# timer.net
KiCad netlist of a schematic drawn in EasyEDA Pro
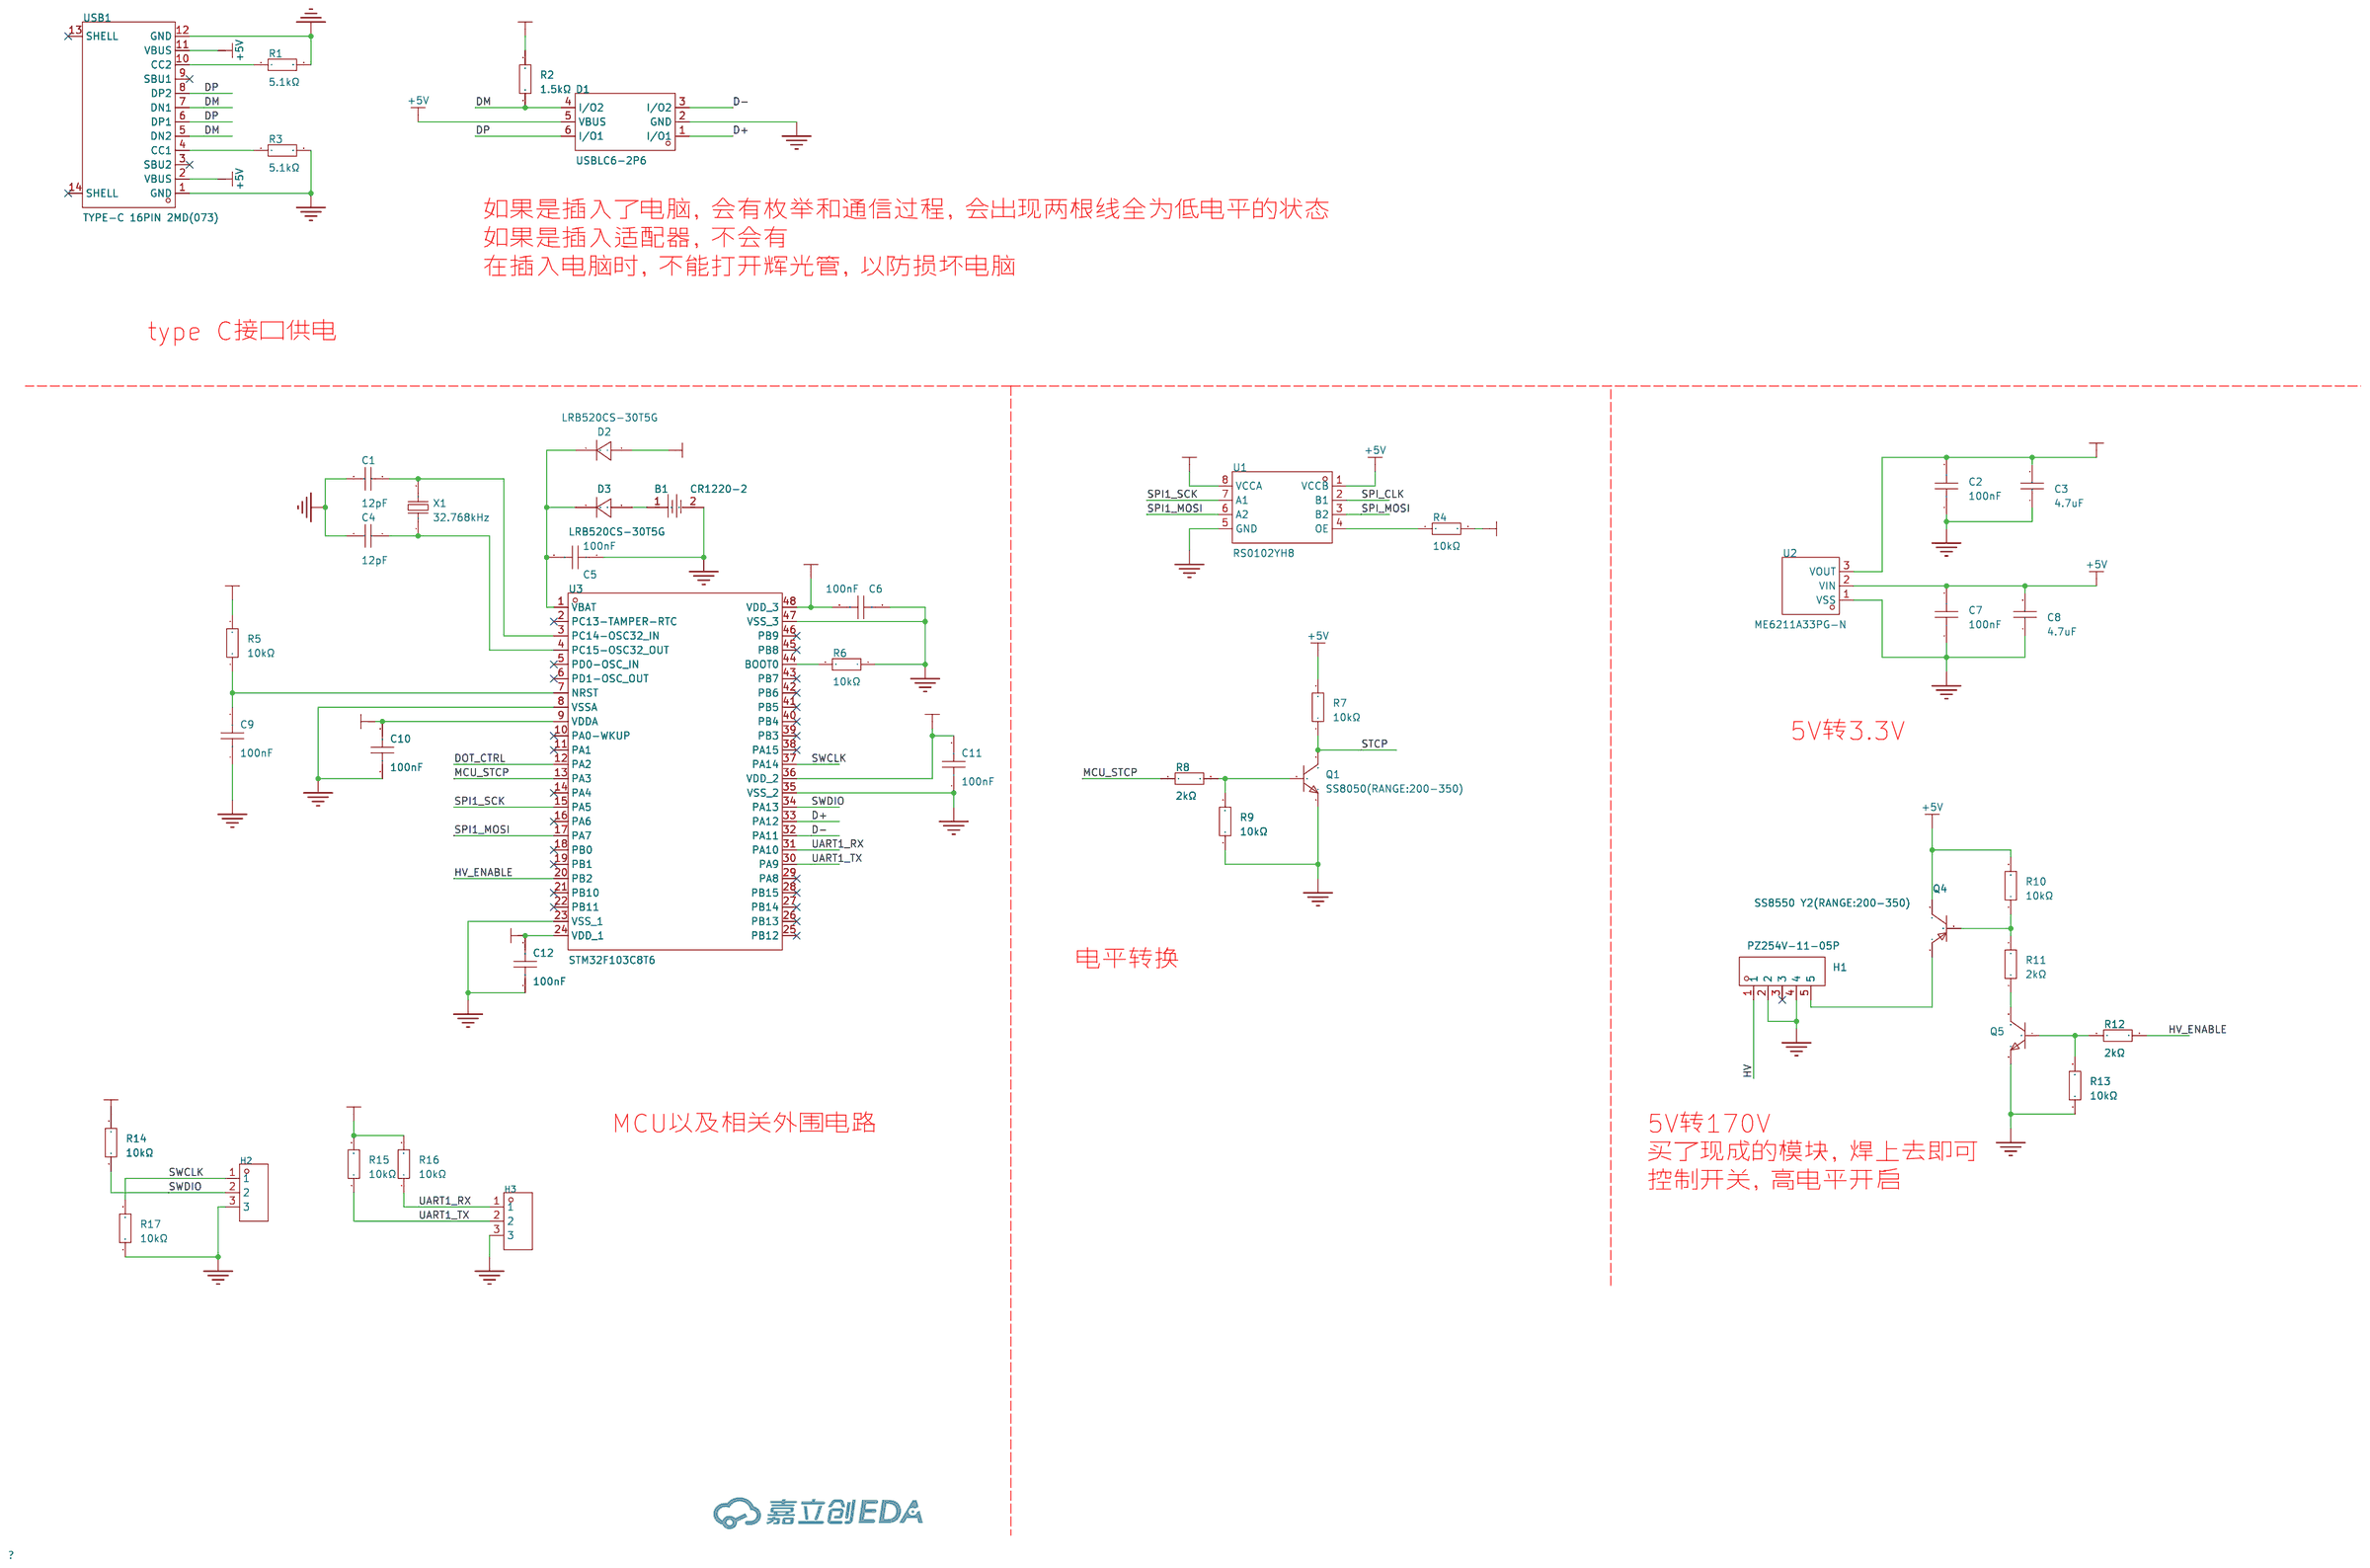
[diagram p0: 控制部分]
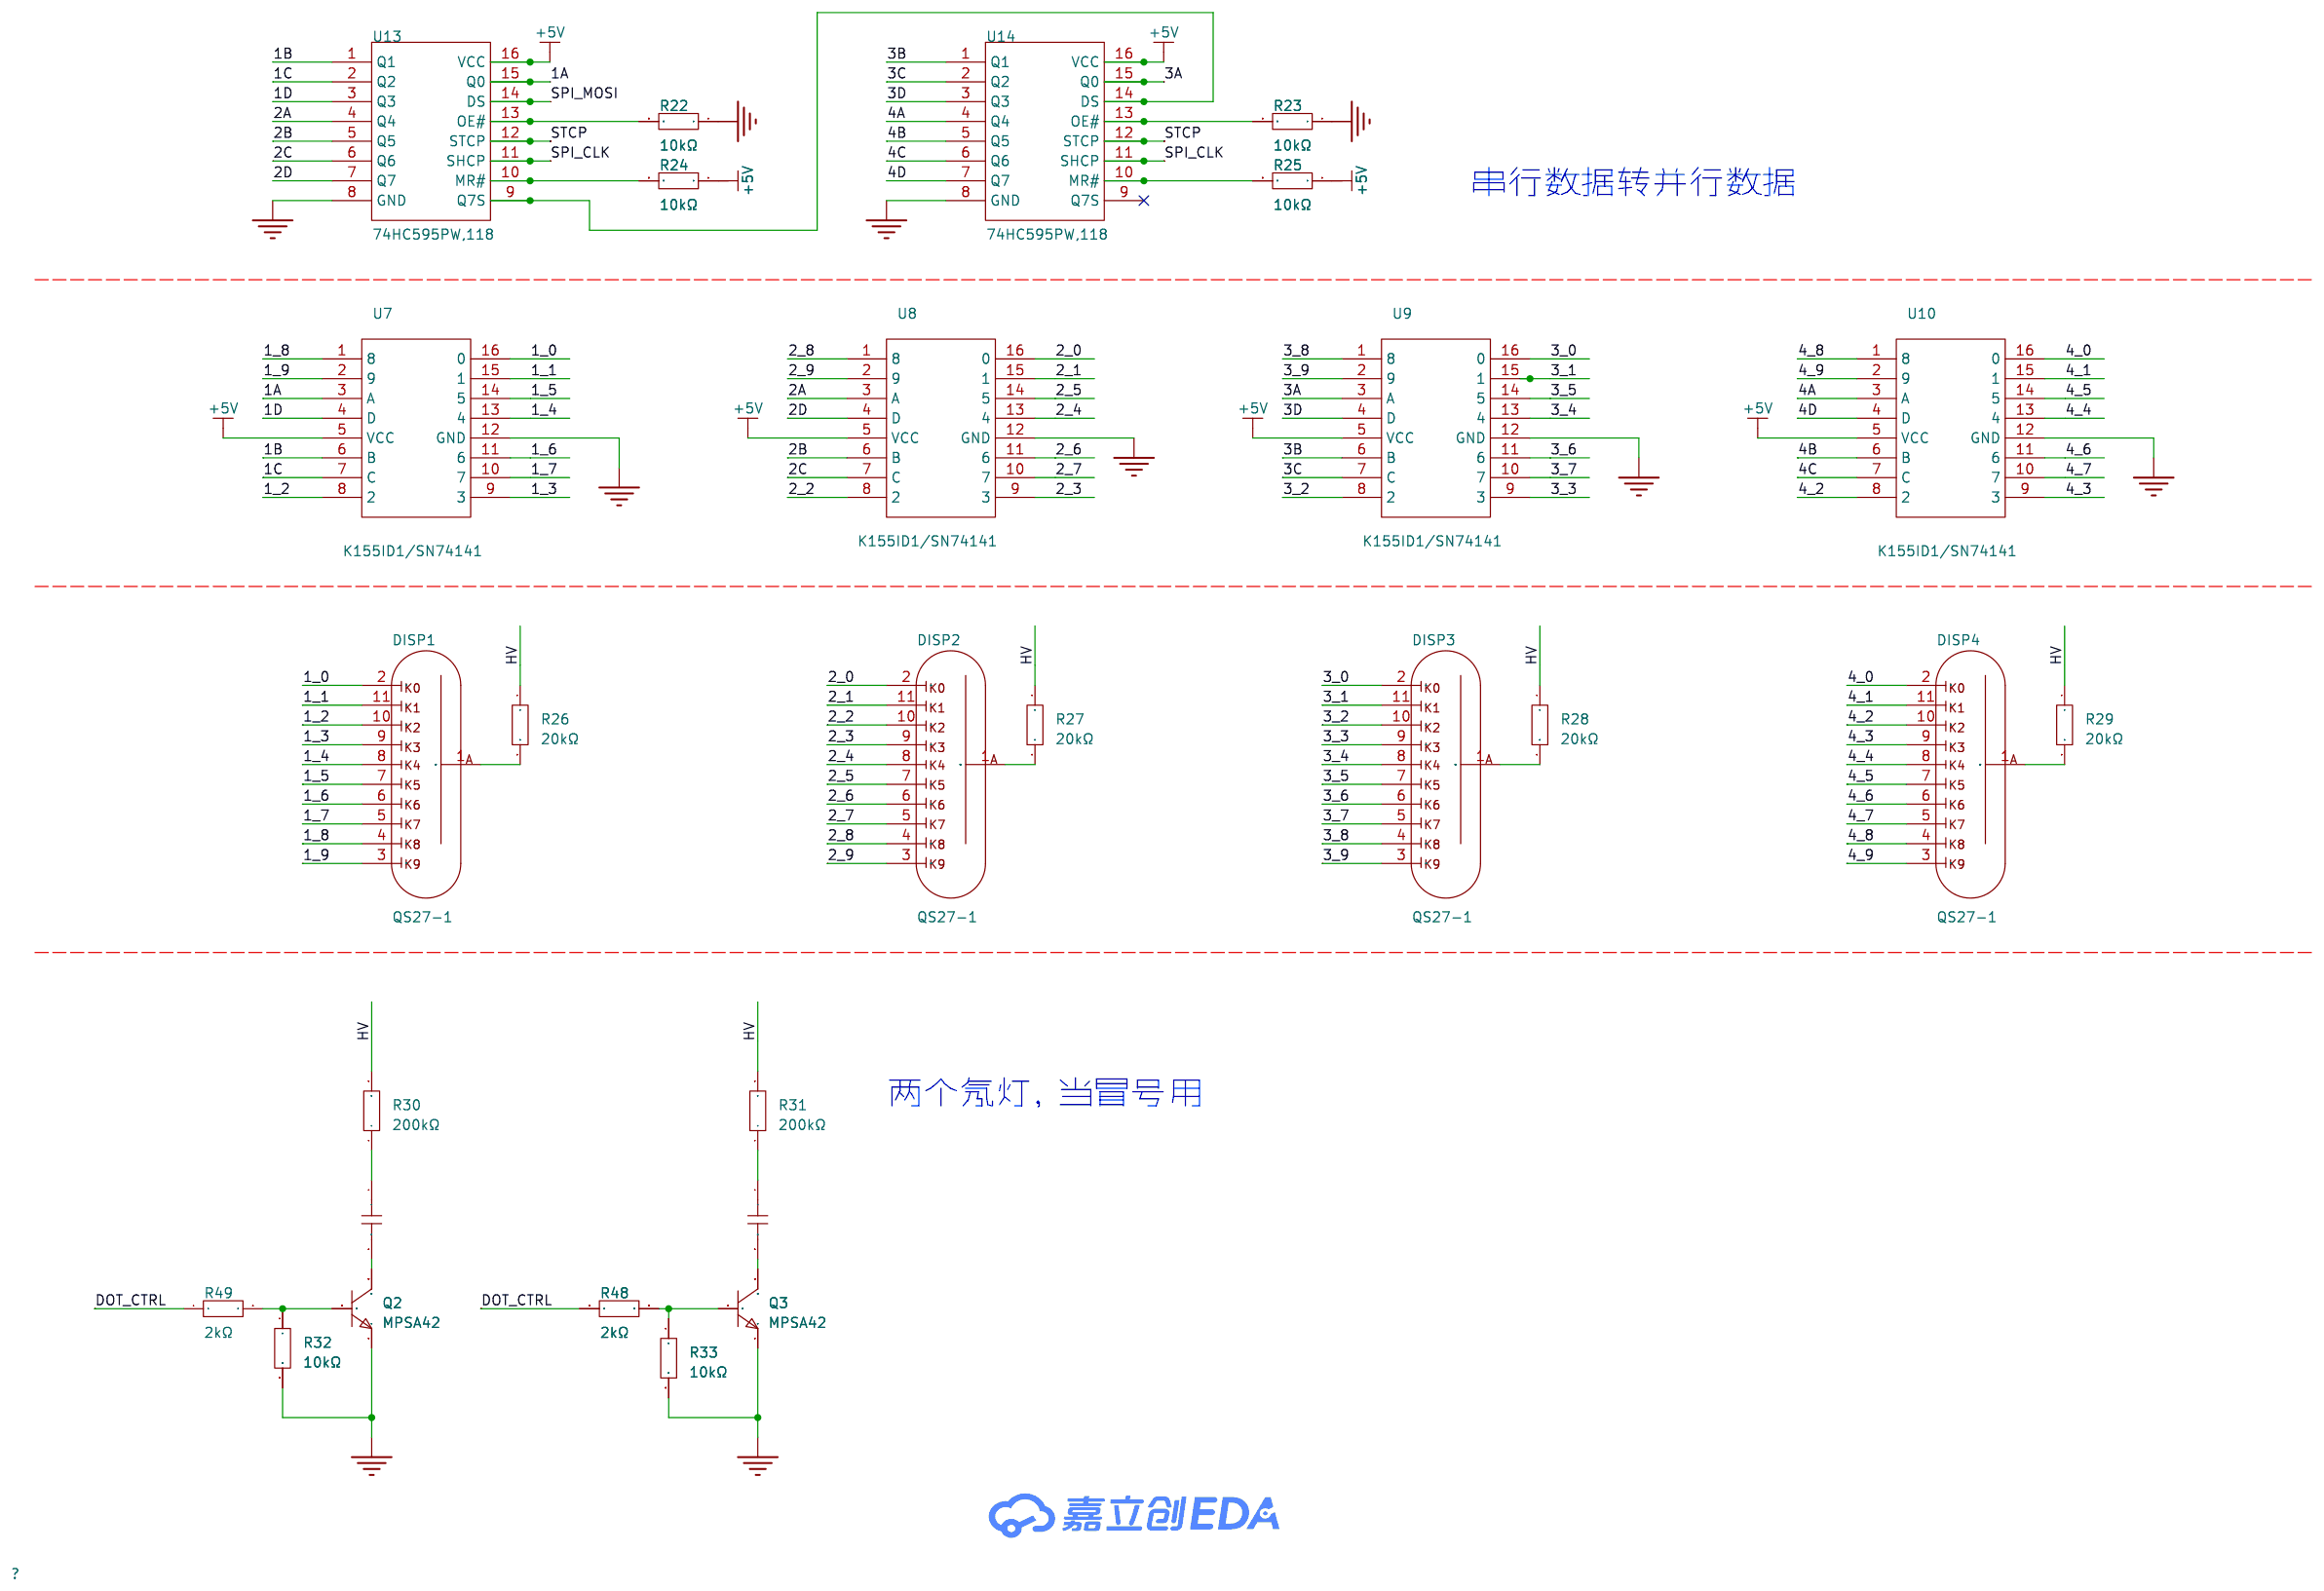
[diagram p1: 显示部分]

(export (version "E")
  (design (tool "Eeschema 10.0.6"))
  (components
    (comp (ref "B1")
      (value "CR1220-2")
      (footprint "easyedapro:BAT-SMD_CR1220-2")
      (description "连接器类型:电池底座;适用电池规格:CR1220;工作温度范围:-;")
      (fields (field (name "Manufacturer") "Q&J"))
      (libsource (lib "easyedapro") (part "CR1220-2"))
    )
    (comp (ref "C1")
      (value "12pF")
      (footprint "easyedapro:C0603")
      (description "容值:12pF;精度:±5%;额定电压:50V;材质(温度系数):NP0;")
      (fields
        (field (name "Manufacturer Part") "CC0603JRNPO9BN120")
        (field (name "Manufacturer") "YAGEO(国巨)")
      )
      (libsource (lib "easyedapro") (part "CC0603JRNPO9BN120"))
    )
    (comp (ref "C2")
      (value "100nF")
      (footprint "easyedapro:C0603")
      (description "容值:100nF;精度:±10%;额定电压:50V;材质(温度系数):X7R;")
      (fields
        (field (name "Manufacturer Part") "CC0603KRX7R9BB104")
        (field (name "Manufacturer") "YAGEO(国巨)")
      )
      (libsource (lib "easyedapro") (part "CC0603KRX7R9BB104"))
    )
    (comp (ref "C3")
      (value "4.7uF")
      (footprint "easyedapro:C0603")
      (description "容值:4.7uF;精度:±10%;额定电压:16V;材质(温度系数):X5R;")
      (fields
        (field (name "Manufacturer Part") "CL10A475KO8NNNC")
        (field (name "Manufacturer") "SAMSUNG(三星)")
      )
      (libsource (lib "easyedapro") (part "CL10A475KO8NNNC"))
    )
    (comp (ref "C4")
      (value "12pF")
      (footprint "easyedapro:C0603")
      (description "容值:12pF;精度:±5%;额定电压:50V;材质(温度系数):NP0;")
      (fields
        (field (name "Manufacturer Part") "CC0603JRNPO9BN120")
        (field (name "Manufacturer") "YAGEO(国巨)")
      )
      (libsource (lib "easyedapro") (part "CC0603JRNPO9BN120"))
    )
    (comp (ref "C5")
      (value "100nF")
      (footprint "easyedapro:C0603")
      (description "容值:100nF;精度:±10%;额定电压:50V;材质(温度系数):X7R;")
      (fields
        (field (name "Manufacturer Part") "CC0603KRX7R9BB104")
        (field (name "Manufacturer") "YAGEO(国巨)")
      )
      (libsource (lib "easyedapro") (part "CC0603KRX7R9BB104"))
    )
    (comp (ref "C6")
      (value "100nF")
      (footprint "easyedapro:C0603")
      (description "容值:100nF;精度:±10%;额定电压:50V;材质(温度系数):X7R;")
      (fields
        (field (name "Manufacturer Part") "CC0603KRX7R9BB104")
        (field (name "Manufacturer") "YAGEO(国巨)")
      )
      (libsource (lib "easyedapro") (part "CC0603KRX7R9BB104"))
    )
    (comp (ref "C7")
      (value "100nF")
      (footprint "easyedapro:C0603")
      (description "容值:100nF;精度:±10%;额定电压:50V;材质(温度系数):X7R;")
      (fields
        (field (name "Manufacturer Part") "CC0603KRX7R9BB104")
        (field (name "Manufacturer") "YAGEO(国巨)")
      )
      (libsource (lib "easyedapro") (part "CC0603KRX7R9BB104"))
    )
    (comp (ref "C8")
      (value "4.7uF")
      (footprint "easyedapro:C0603")
      (description "容值:4.7uF;精度:±10%;额定电压:16V;材质(温度系数):X5R;")
      (fields
        (field (name "Manufacturer Part") "CL10A475KO8NNNC")
        (field (name "Manufacturer") "SAMSUNG(三星)")
      )
      (libsource (lib "easyedapro") (part "CL10A475KO8NNNC"))
    )
    (comp (ref "C9")
      (value "100nF")
      (footprint "easyedapro:C0603")
      (description "容值:100nF;精度:±10%;额定电压:50V;材质(温度系数):X7R;")
      (fields
        (field (name "Manufacturer Part") "CC0603KRX7R9BB104")
        (field (name "Manufacturer") "YAGEO(国巨)")
      )
      (libsource (lib "easyedapro") (part "CC0603KRX7R9BB104"))
    )
    (comp (ref "C10")
      (value "100nF")
      (footprint "easyedapro:C0603")
      (description "容值:100nF;精度:±10%;额定电压:50V;材质(温度系数):X7R;")
      (fields
        (field (name "Manufacturer Part") "CC0603KRX7R9BB104")
        (field (name "Manufacturer") "YAGEO(国巨)")
      )
      (libsource (lib "easyedapro") (part "CC0603KRX7R9BB104"))
    )
    (comp (ref "C11")
      (value "100nF")
      (footprint "easyedapro:C0603")
      (description "容值:100nF;精度:±10%;额定电压:50V;材质(温度系数):X7R;")
      (fields
        (field (name "Manufacturer Part") "CC0603KRX7R9BB104")
        (field (name "Manufacturer") "YAGEO(国巨)")
      )
      (libsource (lib "easyedapro") (part "CC0603KRX7R9BB104"))
    )
    (comp (ref "C12")
      (value "100nF")
      (footprint "easyedapro:C0603")
      (description "容值:100nF;精度:±10%;额定电压:50V;材质(温度系数):X7R;")
      (fields
        (field (name "Manufacturer Part") "CC0603KRX7R9BB104")
        (field (name "Manufacturer") "YAGEO(国巨)")
      )
      (libsource (lib "easyedapro") (part "CC0603KRX7R9BB104"))
    )
    (comp (ref "D1")
      (value "USBLC6-2P6")
      (footprint "easyedapro:SOT-666-6_L1.6-W1.2-P0.50-LS1.6-BL")
      (description "极性:单向;反向截止电压(Vrwm):5V;最大钳位电压:14V;峰值脉冲电流(Ipp):5.5A;峰值脉冲功率(Ppp):80W;击穿电压:6V;")
      (fields (field (name "Manufacturer") "TECH PUBLIC(台舟)"))
      (libsource (lib "easyedapro") (part "USBLC6-2P6_C2827693"))
    )
    (comp (ref "D2")
      (value "LRB520CS-30T5G")
      (footprint "easyedapro:SOD-923_L0.8-W0.6-LS1.0-RD")
      (description "正向压降(Vf):450mV;直流反向耐压(Vr):30V;整流电流:100mA;")
      (fields (field (name "Manufacturer") "LRC(乐山无线电)"))
      (libsource (lib "easyedapro") (part "LRB520CS-30T5G"))
    )
    (comp (ref "D3")
      (value "LRB520CS-30T5G")
      (footprint "easyedapro:SOD-923_L0.8-W0.6-LS1.0-RD")
      (description "正向压降(Vf):450mV;直流反向耐压(Vr):30V;整流电流:100mA;")
      (fields (field (name "Manufacturer") "LRC(乐山无线电)"))
      (libsource (lib "easyedapro") (part "LRB520CS-30T5G"))
    )
    (comp (ref "H1")
      (value "PZ254V-11-05P")
      (footprint "easyedapro:HDR-TH_5P-P2.54-V-M")
      (fields (field (name "Manufacturer") "XFCN(兴飞)"))
      (libsource (lib "easyedapro") (part "PZ254V-11-05P"))
    )
    (comp (ref "H2")
      (value "PZ254V-11-03P")
      (footprint "easyedapro:HDR-TH_3P-P2.54-V-M")
      (fields (field (name "Manufacturer") "XFCN(兴飞)"))
      (libsource (lib "easyedapro") (part "PZ254V-11-03P_C2937625"))
    )
    (comp (ref "H3")
      (value "PZ254V-11-03P")
      (footprint "easyedapro:HDR-TH_3P-P2.54-V-M")
      (fields (field (name "Manufacturer") "XFCN(兴飞)"))
      (libsource (lib "easyedapro") (part "PZ254V-11-03P_C2937625"))
    )
    (comp (ref "Q1")
      (value "SS8050(RANGE:200-350)")
      (footprint "easyedapro:SOT-23-3_L2.9-W1.3-P1.90-LS2.4-BR")
      (description "晶体管类型:NPN;集电极电流(Ic):1.5A;集射极击穿电压(Vceo):25V;功率(Pd):300mW;直流电流增益(hFE@Ic,Vce):200@800mA,1V;")
      (fields (field (name "Manufacturer") "CJ(江苏长电/长晶)"))
      (libsource (lib "easyedapro") (part "SS8050_C2150"))
    )
    (comp (ref "Q4")
      (value "SS8550 Y2(RANGE:200-350)")
      (footprint "easyedapro:SOT-23-3_L2.9-W1.3-P1.90-LS2.4-BR")
      (description "晶体管类型:PNP;集电极电流(Ic):1.5A;集射极击穿电压(Vceo):25V;功率(Pd):300mW;直流电流增益(hFE@Ic,Vce):200@100mA,1V;")
      (fields (field (name "Manufacturer") "CJ(江苏长电/长晶)"))
      (libsource (lib "easyedapro") (part "SS8550_C8542"))
    )
    (comp (ref "Q5")
      (value "SS8050(RANGE:200-350)")
      (footprint "easyedapro:SOT-23-3_L2.9-W1.3-P1.90-LS2.4-BR")
      (description "晶体管类型:NPN;集电极电流(Ic):1.5A;集射极击穿电压(Vceo):25V;功率(Pd):300mW;直流电流增益(hFE@Ic,Vce):200@800mA,1V;")
      (fields (field (name "Manufacturer") "CJ(江苏长电/长晶)"))
      (libsource (lib "easyedapro") (part "SS8050_C2150"))
    )
    (comp (ref "R1")
      (value "5.1kΩ")
      (footprint "easyedapro:R0603")
      (description "电阻类型:厚膜电阻;阻值:5.1kΩ;精度:±1%;功率:100mW;最大工作电压:75V;温度系数:±100ppm/°C;")
      (fields
        (field (name "Manufacturer Part") "0603WAF5101T5E")
        (field (name "Manufacturer") "UNI-ROYAL(厚声)")
      )
      (libsource (lib "easyedapro") (part "0603WAF5101T5E"))
    )
    (comp (ref "R2")
      (value "1.5kΩ")
      (footprint "easyedapro:R0603")
      (description "电阻类型:厚膜电阻;阻值:1.5kΩ;精度:±1%;功率:100mW;最大工作电压:75V;温度系数:±100ppm/°C;")
      (fields
        (field (name "Manufacturer Part") "0603WAF1501T5E")
        (field (name "Manufacturer") "UNI-ROYAL(厚声)")
      )
      (libsource (lib "easyedapro") (part "0603WAF1501T5E"))
    )
    (comp (ref "R3")
      (value "5.1kΩ")
      (footprint "easyedapro:R0603")
      (description "电阻类型:厚膜电阻;阻值:5.1kΩ;精度:±1%;功率:100mW;最大工作电压:75V;温度系数:±100ppm/°C;")
      (fields
        (field (name "Manufacturer Part") "0603WAF5101T5E")
        (field (name "Manufacturer") "UNI-ROYAL(厚声)")
      )
      (libsource (lib "easyedapro") (part "0603WAF5101T5E"))
    )
    (comp (ref "R4")
      (value "10kΩ")
      (footprint "easyedapro:R0603")
      (description "电阻类型:厚膜电阻;阻值:10kΩ;精度:±1%;功率:100mW;最大工作电压:75V;温度系数:±100ppm/°C;")
      (fields
        (field (name "Manufacturer Part") "0603WAF1002T5E")
        (field (name "Manufacturer") "UNI-ROYAL(厚声)")
      )
      (libsource (lib "easyedapro") (part "0603WAF1002T5E"))
    )
    (comp (ref "R5")
      (value "10kΩ")
      (footprint "easyedapro:R0603")
      (description "电阻类型:厚膜电阻;阻值:10kΩ;精度:±1%;功率:100mW;最大工作电压:75V;温度系数:±100ppm/°C;")
      (fields
        (field (name "Manufacturer Part") "0603WAF1002T5E")
        (field (name "Manufacturer") "UNI-ROYAL(厚声)")
      )
      (libsource (lib "easyedapro") (part "0603WAF1002T5E"))
    )
    (comp (ref "R6")
      (value "10kΩ")
      (footprint "easyedapro:R0603")
      (description "电阻类型:厚膜电阻;阻值:10kΩ;精度:±1%;功率:100mW;最大工作电压:75V;温度系数:±100ppm/°C;")
      (fields
        (field (name "Manufacturer Part") "0603WAF1002T5E")
        (field (name "Manufacturer") "UNI-ROYAL(厚声)")
      )
      (libsource (lib "easyedapro") (part "0603WAF1002T5E"))
    )
    (comp (ref "R7")
      (value "10kΩ")
      (footprint "easyedapro:R0603")
      (description "电阻类型:厚膜电阻;阻值:10kΩ;精度:±1%;功率:100mW;最大工作电压:75V;温度系数:±100ppm/°C;")
      (fields
        (field (name "Manufacturer Part") "0603WAF1002T5E")
        (field (name "Manufacturer") "UNI-ROYAL(厚声)")
      )
      (libsource (lib "easyedapro") (part "0603WAF1002T5E"))
    )
    (comp (ref "R8")
      (value "2kΩ")
      (footprint "easyedapro:R0603")
      (description "电阻类型:厚膜电阻;阻值:2kΩ;精度:±1%;功率:100mW;最大工作电压:75V;温度系数:±100ppm/°C;")
      (fields
        (field (name "Manufacturer Part") "0603WAF2001T5E")
        (field (name "Manufacturer") "UNI-ROYAL(厚声)")
      )
      (libsource (lib "easyedapro") (part "0603WAF2001T5E"))
    )
    (comp (ref "R9")
      (value "10kΩ")
      (footprint "easyedapro:R0603")
      (description "电阻类型:厚膜电阻;阻值:10kΩ;精度:±1%;功率:100mW;最大工作电压:75V;温度系数:±100ppm/°C;")
      (fields
        (field (name "Manufacturer Part") "0603WAF1002T5E")
        (field (name "Manufacturer") "UNI-ROYAL(厚声)")
      )
      (libsource (lib "easyedapro") (part "0603WAF1002T5E"))
    )
    (comp (ref "R10")
      (value "10kΩ")
      (footprint "easyedapro:R0603")
      (description "电阻类型:厚膜电阻;阻值:10kΩ;精度:±1%;功率:100mW;最大工作电压:75V;温度系数:±100ppm/°C;")
      (fields
        (field (name "Manufacturer Part") "0603WAF1002T5E")
        (field (name "Manufacturer") "UNI-ROYAL(厚声)")
      )
      (libsource (lib "easyedapro") (part "0603WAF1002T5E"))
    )
    (comp (ref "R11")
      (value "2kΩ")
      (footprint "easyedapro:R0603")
      (description "电阻类型:厚膜电阻;阻值:2kΩ;精度:±1%;功率:100mW;最大工作电压:75V;温度系数:±100ppm/°C;")
      (fields
        (field (name "Manufacturer Part") "0603WAF2001T5E")
        (field (name "Manufacturer") "UNI-ROYAL(厚声)")
      )
      (libsource (lib "easyedapro") (part "0603WAF2001T5E"))
    )
    (comp (ref "R12")
      (value "2kΩ")
      (footprint "easyedapro:R0603")
      (description "电阻类型:厚膜电阻;阻值:2kΩ;精度:±1%;功率:100mW;最大工作电压:75V;温度系数:±100ppm/°C;")
      (fields
        (field (name "Manufacturer Part") "0603WAF2001T5E")
        (field (name "Manufacturer") "UNI-ROYAL(厚声)")
      )
      (libsource (lib "easyedapro") (part "0603WAF2001T5E"))
    )
    (comp (ref "R13")
      (value "10kΩ")
      (footprint "easyedapro:R0603")
      (description "电阻类型:厚膜电阻;阻值:10kΩ;精度:±1%;功率:100mW;最大工作电压:75V;温度系数:±100ppm/°C;")
      (fields
        (field (name "Manufacturer Part") "0603WAF1002T5E")
        (field (name "Manufacturer") "UNI-ROYAL(厚声)")
      )
      (libsource (lib "easyedapro") (part "0603WAF1002T5E"))
    )
    (comp (ref "R14")
      (value "10kΩ")
      (footprint "easyedapro:R0603")
      (description "电阻类型:厚膜电阻;阻值:10kΩ;精度:±1%;功率:100mW;最大工作电压:75V;温度系数:±100ppm/°C;")
      (fields
        (field (name "Manufacturer Part") "0603WAF1002T5E")
        (field (name "Manufacturer") "UNI-ROYAL(厚声)")
      )
      (libsource (lib "easyedapro") (part "0603WAF1002T5E"))
    )
    (comp (ref "R15")
      (value "10kΩ")
      (footprint "easyedapro:R0603")
      (description "电阻类型:厚膜电阻;阻值:10kΩ;精度:±1%;功率:100mW;最大工作电压:75V;温度系数:±100ppm/°C;")
      (fields
        (field (name "Manufacturer Part") "0603WAF1002T5E")
        (field (name "Manufacturer") "UNI-ROYAL(厚声)")
      )
      (libsource (lib "easyedapro") (part "0603WAF1002T5E"))
    )
    (comp (ref "R16")
      (value "10kΩ")
      (footprint "easyedapro:R0603")
      (description "电阻类型:厚膜电阻;阻值:10kΩ;精度:±1%;功率:100mW;最大工作电压:75V;温度系数:±100ppm/°C;")
      (fields
        (field (name "Manufacturer Part") "0603WAF1002T5E")
        (field (name "Manufacturer") "UNI-ROYAL(厚声)")
      )
      (libsource (lib "easyedapro") (part "0603WAF1002T5E"))
    )
    (comp (ref "R17")
      (value "10kΩ")
      (footprint "easyedapro:R0603")
      (description "电阻类型:厚膜电阻;阻值:10kΩ;精度:±1%;功率:100mW;最大工作电压:75V;温度系数:±100ppm/°C;")
      (fields
        (field (name "Manufacturer Part") "0603WAF1002T5E")
        (field (name "Manufacturer") "UNI-ROYAL(厚声)")
      )
      (libsource (lib "easyedapro") (part "0603WAF1002T5E"))
    )
    (comp (ref "U1")
      (value "RS0102YH8")
      (footprint "easyedapro:SOT-23-8_L3.0-W1.7-P0.65-LS2.8-BL")
      (description "数据速率:24Mbps;电压(VCCA):1.65V~5.5V;电压(VCCB):2.3V~5.5V;电路数:1;每个电路通道数:2;")
      (fields (field (name "Manufacturer") "RUNIC(润石)"))
      (libsource (lib "easyedapro") (part "RS0102YH8"))
    )
    (comp (ref "U2")
      (value "ME6211A33PG-N")
      (footprint "easyedapro:SOT-89_L4.5-W2.5-P1.50-LS4.2-BR")
      (description "输出类型:固定;最大输入电压:6V;输出电压:3.3V;最大输出电流:500mA;电源纹波抑制比(PSRR):70dB;输出极性:正极;")
      (fields (field (name "Manufacturer") "MICRONE(南京微盟)"))
      (libsource (lib "easyedapro") (part "ME6211A33PG-N"))
    )
    (comp (ref "U3")
      (value "STM32F103C8T6")
      (footprint "easyedapro:LQFP-48_L7.0-W7.0-P0.50-LS9.0-BL")
      (description "CPU内核:ARM-M3;CPU最大主频:72MHz;应用领域:-;")
      (fields (field (name "Manufacturer") "ST(意法半导体)"))
      (libsource (lib "easyedapro") (part "STM32F103C8T6"))
    )
    (comp (ref "USB1")
      (value "TYPE-C 16PIN 2MD(073)")
      (footprint "easyedapro:USB-C-SMD_TYPE-C-6PIN-2MD-073")
      (description "连接器类型:Type-C;标准:USB 3.1;公母:母;安装方式:卧贴;触点数量:16P;端口数量:1;额定电流 - 电源:5A;工作温度范围:-25°C~+85°C;")
      (fields (field (name "Manufacturer") "SHOU HAN(首韩)"))
      (libsource (lib "easyedapro") (part "TYPE-C 16PIN 2MD(073)"))
    )
    (comp (ref "X1")
      (value "32.768kHz")
      (footprint "easyedapro:FC-135R_L3.2-W1.5")
      (description "晶振类型:贴片晶振;频率:32.768kHz;常温频差:±20ppm;负载电容:12.5pF;")
      (fields (field (name "Manufacturer Part") "Q13FC13500004") (field (name "Manufacturer") "EPSON(爱普生)"))
      (libsource (lib "easyedapro") (part "Q13FC1350000400"))
    )
    (comp (ref "DISP1")
      (value "QS27-1")
      (footprint "easyedapro:QS27-1")
      (libsource (lib "easyedapro") (part "QS27-1"))
    )
    (comp (ref "DISP2")
      (value "QS27-1")
      (footprint "easyedapro:QS27-1")
      (libsource (lib "easyedapro") (part "QS27-1"))
    )
    (comp (ref "DISP3")
      (value "QS27-1")
      (footprint "easyedapro:QS27-1")
      (libsource (lib "easyedapro") (part "QS27-1"))
    )
    (comp (ref "DISP4")
      (value "QS27-1")
      (footprint "easyedapro:QS27-1")
      (libsource (lib "easyedapro") (part "QS27-1"))
    )
    (comp (ref "NE1") (value "NE") (footprint "easyedapro:NE") (libsource (lib "easyedapro") (part "NE")))
    (comp (ref "NE2") (value "NE") (footprint "easyedapro:NE") (libsource (lib "easyedapro") (part "NE")))
    (comp (ref "Q2")
      (value "MPSA42")
      (footprint "easyedapro:TO-92-3_L4.9-W3.7-P1.27-L")
      (description "晶体管类型:NPN;集电极电流(Ic):200mA;集射极击穿电压(Vceo):305V;功率(Pd):625mW;直流电流增益(hFE@Ic,Vce):60@1mA,10V;")
      (fields (field (name "Manufacturer") "CJ(江苏长电/长晶)"))
      (libsource (lib "easyedapro") (part "MPSA42_C2991971"))
    )
    (comp (ref "Q3")
      (value "MPSA42")
      (footprint "easyedapro:TO-92-3_L4.9-W3.7-P1.27-L")
      (description "晶体管类型:NPN;集电极电流(Ic):200mA;集射极击穿电压(Vceo):305V;功率(Pd):625mW;直流电流增益(hFE@Ic,Vce):60@1mA,10V;")
      (fields (field (name "Manufacturer") "CJ(江苏长电/长晶)"))
      (libsource (lib "easyedapro") (part "MPSA42_C2991971"))
    )
    (comp (ref "R22")
      (value "10kΩ")
      (footprint "easyedapro:R0603")
      (description "电阻类型:厚膜电阻;阻值:10kΩ;精度:±1%;功率:100mW;最大工作电压:75V;温度系数:±100ppm/°C;")
      (fields
        (field (name "Manufacturer Part") "0603WAF1002T5E")
        (field (name "Manufacturer") "UNI-ROYAL(厚声)")
      )
      (libsource (lib "easyedapro") (part "0603WAF1002T5E"))
    )
    (comp (ref "R23")
      (value "10kΩ")
      (footprint "easyedapro:R0603")
      (description "电阻类型:厚膜电阻;阻值:10kΩ;精度:±1%;功率:100mW;最大工作电压:75V;温度系数:±100ppm/°C;")
      (fields
        (field (name "Manufacturer Part") "0603WAF1002T5E")
        (field (name "Manufacturer") "UNI-ROYAL(厚声)")
      )
      (libsource (lib "easyedapro") (part "0603WAF1002T5E"))
    )
    (comp (ref "R24")
      (value "10kΩ")
      (footprint "easyedapro:R0603")
      (description "电阻类型:厚膜电阻;阻值:10kΩ;精度:±1%;功率:100mW;最大工作电压:75V;温度系数:±100ppm/°C;")
      (fields
        (field (name "Manufacturer Part") "0603WAF1002T5E")
        (field (name "Manufacturer") "UNI-ROYAL(厚声)")
      )
      (libsource (lib "easyedapro") (part "0603WAF1002T5E"))
    )
    (comp (ref "R25")
      (value "10kΩ")
      (footprint "easyedapro:R0603")
      (description "电阻类型:厚膜电阻;阻值:10kΩ;精度:±1%;功率:100mW;最大工作电压:75V;温度系数:±100ppm/°C;")
      (fields
        (field (name "Manufacturer Part") "0603WAF1002T5E")
        (field (name "Manufacturer") "UNI-ROYAL(厚声)")
      )
      (libsource (lib "easyedapro") (part "0603WAF1002T5E"))
    )
    (comp (ref "R26")
      (value "20kΩ")
      (footprint "easyedapro:R1206")
      (description "电阻类型:厚膜电阻;阻值:20kΩ;精度:±5%;功率:250mW;最大工作电压:200V;温度系数:±100ppm/°C;")
      (fields
        (field (name "Manufacturer Part") "1206W4J0203T5E")
        (field (name "Manufacturer") "UNI-ROYAL(厚声)")
      )
      (libsource (lib "easyedapro") (part "1206W4J0203T5E"))
    )
    (comp (ref "R27")
      (value "20kΩ")
      (footprint "easyedapro:R1206")
      (description "电阻类型:厚膜电阻;阻值:20kΩ;精度:±5%;功率:250mW;最大工作电压:200V;温度系数:±100ppm/°C;")
      (fields
        (field (name "Manufacturer Part") "1206W4J0203T5E")
        (field (name "Manufacturer") "UNI-ROYAL(厚声)")
      )
      (libsource (lib "easyedapro") (part "1206W4J0203T5E"))
    )
    (comp (ref "R28")
      (value "20kΩ")
      (footprint "easyedapro:R1206")
      (description "电阻类型:厚膜电阻;阻值:20kΩ;精度:±5%;功率:250mW;最大工作电压:200V;温度系数:±100ppm/°C;")
      (fields
        (field (name "Manufacturer Part") "1206W4J0203T5E")
        (field (name "Manufacturer") "UNI-ROYAL(厚声)")
      )
      (libsource (lib "easyedapro") (part "1206W4J0203T5E"))
    )
    (comp (ref "R29")
      (value "20kΩ")
      (footprint "easyedapro:R1206")
      (description "电阻类型:厚膜电阻;阻值:20kΩ;精度:±5%;功率:250mW;最大工作电压:200V;温度系数:±100ppm/°C;")
      (fields
        (field (name "Manufacturer Part") "1206W4J0203T5E")
        (field (name "Manufacturer") "UNI-ROYAL(厚声)")
      )
      (libsource (lib "easyedapro") (part "1206W4J0203T5E"))
    )
    (comp (ref "R30")
      (value "200kΩ")
      (footprint "easyedapro:R1206")
      (description "电阻类型:厚膜电阻;阻值:200kΩ;精度:±1%;功率:250mW;最大工作电压:200V;温度系数:±100ppm/°C;")
      (fields (field (name "Manufacturer Part") "RC1206FR-07200KL") (field (name "Manufacturer") "YAGEO(国巨)"))
      (libsource (lib "easyedapro") (part "RC1206FR-07200KL"))
    )
    (comp (ref "R31")
      (value "200kΩ")
      (footprint "easyedapro:R1206")
      (description "电阻类型:厚膜电阻;阻值:200kΩ;精度:±1%;功率:250mW;最大工作电压:200V;温度系数:±100ppm/°C;")
      (fields (field (name "Manufacturer Part") "RC1206FR-07200KL") (field (name "Manufacturer") "YAGEO(国巨)"))
      (libsource (lib "easyedapro") (part "RC1206FR-07200KL"))
    )
    (comp (ref "R32")
      (value "10kΩ")
      (footprint "easyedapro:R0603")
      (description "电阻类型:厚膜电阻;阻值:10kΩ;精度:±1%;功率:100mW;最大工作电压:75V;温度系数:±100ppm/°C;")
      (fields
        (field (name "Manufacturer Part") "0603WAF1002T5E")
        (field (name "Manufacturer") "UNI-ROYAL(厚声)")
      )
      (libsource (lib "easyedapro") (part "0603WAF1002T5E"))
    )
    (comp (ref "R33")
      (value "10kΩ")
      (footprint "easyedapro:R0603")
      (description "电阻类型:厚膜电阻;阻值:10kΩ;精度:±1%;功率:100mW;最大工作电压:75V;温度系数:±100ppm/°C;")
      (fields
        (field (name "Manufacturer Part") "0603WAF1002T5E")
        (field (name "Manufacturer") "UNI-ROYAL(厚声)")
      )
      (libsource (lib "easyedapro") (part "0603WAF1002T5E"))
    )
    (comp (ref "R48")
      (value "2kΩ")
      (footprint "easyedapro:R0603")
      (description "电阻类型:厚膜电阻;阻值:2kΩ;精度:±1%;功率:100mW;最大工作电压:75V;温度系数:±100ppm/°C;")
      (fields
        (field (name "Manufacturer Part") "0603WAF2001T5E")
        (field (name "Manufacturer") "UNI-ROYAL(厚声)")
      )
      (libsource (lib "easyedapro") (part "0603WAF2001T5E"))
    )
    (comp (ref "R49")
      (value "2kΩ")
      (footprint "easyedapro:R0603")
      (description "电阻类型:厚膜电阻;阻值:2kΩ;精度:±1%;功率:100mW;最大工作电压:75V;温度系数:±100ppm/°C;")
      (fields
        (field (name "Manufacturer Part") "0603WAF2001T5E")
        (field (name "Manufacturer") "UNI-ROYAL(厚声)")
      )
      (libsource (lib "easyedapro") (part "0603WAF2001T5E"))
    )
    (comp (ref "U7")
      (value "K155ID1/SN74141")
      (footprint "easyedapro:DIP16")
      (libsource (lib "easyedapro") (part "K155ID1/SN74141"))
    )
    (comp (ref "U8")
      (value "K155ID1/SN74141")
      (footprint "easyedapro:DIP16")
      (libsource (lib "easyedapro") (part "K155ID1/SN74141"))
    )
    (comp (ref "U9")
      (value "K155ID1/SN74141")
      (footprint "easyedapro:DIP16")
      (libsource (lib "easyedapro") (part "K155ID1/SN74141"))
    )
    (comp (ref "U10")
      (value "K155ID1/SN74141")
      (footprint "easyedapro:DIP16")
      (libsource (lib "easyedapro") (part "K155ID1/SN74141"))
    )
    (comp (ref "U13")
      (value "74HC595PW,118")
      (footprint "easyedapro:TSSOP-16_L5.0-W4.4-P0.65-LS6.4-BL")
      (description "功能:串行至串行或并行;电源电压:2V~6V;元件数:1;每个元件位数:8;")
      (fields (field (name "Manufacturer") "Nexperia(安世)"))
      (libsource (lib "easyedapro") (part "74HC595PW,118"))
    )
    (comp (ref "U14")
      (value "74HC595PW,118")
      (footprint "easyedapro:TSSOP-16_L5.0-W4.4-P0.65-LS6.4-BL")
      (description "功能:串行至串行或并行;电源电压:2V~6V;元件数:1;每个元件位数:8;")
      (fields (field (name "Manufacturer") "Nexperia(安世)"))
      (libsource (lib "easyedapro") (part "74HC595PW,118"))
    )
  )
  (nets
    (net (code "1") (name "+5V") (class "Default")
      (node (ref "C7") (pin "2") (pinfunction "2_2") (pintype "unspecified"))
      (node (ref "C8") (pin "2") (pinfunction "2_2") (pintype "input"))
      (node (ref "D1") (pin "5") (pinfunction "VBUS_5") (pintype "unspecified"))
      (node (ref "Q4") (pin "3") (pinfunction "C_3") (pintype "unspecified"))
      (node (ref "R10") (pin "2") (pinfunction "2_2") (pintype "input"))
      (node (ref "R24") (pin "1") (pinfunction "1_1") (pintype "input"))
      (node (ref "R25") (pin "1") (pinfunction "1_1") (pintype "input"))
      (node (ref "R7") (pin "2") (pinfunction "2_2") (pintype "input"))
      (node (ref "U1") (pin "1") (pinfunction "VCCB_1") (pintype "unspecified"))
      (node (ref "U10") (pin "5") (pinfunction "VCC_5") (pintype "unspecified"))
      (node (ref "U13") (pin "16") (pinfunction "VCC_16") (pintype "unspecified"))
      (node (ref "U14") (pin "16") (pinfunction "VCC_16") (pintype "unspecified"))
      (node (ref "U2") (pin "2") (pinfunction "VIN_2") (pintype "unspecified"))
      (node (ref "U7") (pin "5") (pinfunction "VCC_5") (pintype "unspecified"))
      (node (ref "U8") (pin "5") (pinfunction "VCC_5") (pintype "unspecified"))
      (node (ref "U9") (pin "5") (pinfunction "VCC_5") (pintype "unspecified"))
      (node (ref "USB1") (pin "11") (pinfunction "VBUS_11") (pintype "unspecified"))
      (node (ref "USB1") (pin "2") (pinfunction "VBUS_2") (pintype "unspecified"))
    )
    (net (code "2") (name "1A") (class "Default")
      (node (ref "U13") (pin "15") (pinfunction "Q0_15") (pintype "unspecified"))
      (node (ref "U7") (pin "3") (pinfunction "A_3") (pintype "unspecified"))
    )
    (net (code "3") (name "1B") (class "Default")
      (node (ref "U13") (pin "1") (pinfunction "Q1_1") (pintype "unspecified"))
      (node (ref "U7") (pin "6") (pinfunction "B_6") (pintype "unspecified"))
    )
    (net (code "4") (name "1C") (class "Default")
      (node (ref "U13") (pin "2") (pinfunction "Q2_2") (pintype "unspecified"))
      (node (ref "U7") (pin "7") (pinfunction "C_7") (pintype "unspecified"))
    )
    (net (code "5") (name "1D") (class "Default")
      (node (ref "U13") (pin "3") (pinfunction "Q3_3") (pintype "unspecified"))
      (node (ref "U7") (pin "4") (pinfunction "D_4") (pintype "unspecified"))
    )
    (net (code "6") (name "1_0") (class "Default")
      (node (ref "DISP1") (pin "2") (pinfunction "K0_2") (pintype "input"))
      (node (ref "U7") (pin "16") (pinfunction "0_16") (pintype "unspecified"))
    )
    (net (code "7") (name "1_1") (class "Default")
      (node (ref "DISP1") (pin "11") (pinfunction "K1_11") (pintype "input"))
      (node (ref "U7") (pin "15") (pinfunction "1_15") (pintype "unspecified"))
    )
    (net (code "8") (name "1_2") (class "Default")
      (node (ref "DISP1") (pin "10") (pinfunction "K2_10") (pintype "input"))
      (node (ref "U7") (pin "8") (pinfunction "2_8") (pintype "unspecified"))
    )
    (net (code "9") (name "1_3") (class "Default")
      (node (ref "DISP1") (pin "9") (pinfunction "K3_9") (pintype "input"))
      (node (ref "U7") (pin "9") (pinfunction "3_9") (pintype "unspecified"))
    )
    (net (code "10") (name "1_4") (class "Default")
      (node (ref "DISP1") (pin "8") (pinfunction "K4_8") (pintype "input"))
      (node (ref "U7") (pin "13") (pinfunction "4_13") (pintype "unspecified"))
    )
    (net (code "11") (name "1_5") (class "Default")
      (node (ref "DISP1") (pin "7") (pinfunction "K5_7") (pintype "input"))
      (node (ref "U7") (pin "14") (pinfunction "5_14") (pintype "unspecified"))
    )
    (net (code "12") (name "1_6") (class "Default")
      (node (ref "DISP1") (pin "6") (pinfunction "K6_6") (pintype "input"))
      (node (ref "U7") (pin "11") (pinfunction "6_11") (pintype "unspecified"))
    )
    (net (code "13") (name "1_7") (class "Default")
      (node (ref "DISP1") (pin "5") (pinfunction "K7_5") (pintype "input"))
      (node (ref "U7") (pin "10") (pinfunction "7_10") (pintype "unspecified"))
    )
    (net (code "14") (name "1_8") (class "Default")
      (node (ref "DISP1") (pin "4") (pinfunction "K8_4") (pintype "input"))
      (node (ref "U7") (pin "1") (pinfunction "8_1") (pintype "unspecified"))
    )
    (net (code "15") (name "1_9") (class "Default")
      (node (ref "DISP1") (pin "3") (pinfunction "K9_3") (pintype "input"))
      (node (ref "U7") (pin "2") (pinfunction "9_2") (pintype "unspecified"))
    )
    (net (code "16") (name "2A") (class "Default")
      (node (ref "U13") (pin "4") (pinfunction "Q4_4") (pintype "unspecified"))
      (node (ref "U8") (pin "3") (pinfunction "A_3") (pintype "unspecified"))
    )
    (net (code "17") (name "2B") (class "Default")
      (node (ref "U13") (pin "5") (pinfunction "Q5_5") (pintype "unspecified"))
      (node (ref "U8") (pin "6") (pinfunction "B_6") (pintype "unspecified"))
    )
    (net (code "18") (name "2C") (class "Default")
      (node (ref "U13") (pin "6") (pinfunction "Q6_6") (pintype "unspecified"))
      (node (ref "U8") (pin "7") (pinfunction "C_7") (pintype "unspecified"))
    )
    (net (code "19") (name "2D") (class "Default")
      (node (ref "U13") (pin "7") (pinfunction "Q7_7") (pintype "unspecified"))
      (node (ref "U8") (pin "4") (pinfunction "D_4") (pintype "unspecified"))
    )
    (net (code "20") (name "2_0") (class "Default")
      (node (ref "DISP2") (pin "2") (pinfunction "K0_2") (pintype "input"))
      (node (ref "U8") (pin "16") (pinfunction "0_16") (pintype "unspecified"))
    )
    (net (code "21") (name "2_1") (class "Default")
      (node (ref "DISP2") (pin "11") (pinfunction "K1_11") (pintype "input"))
      (node (ref "U8") (pin "15") (pinfunction "1_15") (pintype "unspecified"))
    )
    (net (code "22") (name "2_2") (class "Default")
      (node (ref "DISP2") (pin "10") (pinfunction "K2_10") (pintype "input"))
      (node (ref "U8") (pin "8") (pinfunction "2_8") (pintype "unspecified"))
    )
    (net (code "23") (name "2_3") (class "Default")
      (node (ref "DISP2") (pin "9") (pinfunction "K3_9") (pintype "input"))
      (node (ref "U8") (pin "9") (pinfunction "3_9") (pintype "unspecified"))
    )
    (net (code "24") (name "2_4") (class "Default")
      (node (ref "DISP2") (pin "8") (pinfunction "K4_8") (pintype "input"))
      (node (ref "U8") (pin "13") (pinfunction "4_13") (pintype "unspecified"))
    )
    (net (code "25") (name "2_5") (class "Default")
      (node (ref "DISP2") (pin "7") (pinfunction "K5_7") (pintype "input"))
      (node (ref "U8") (pin "14") (pinfunction "5_14") (pintype "unspecified"))
    )
    (net (code "26") (name "2_6") (class "Default")
      (node (ref "DISP2") (pin "6") (pinfunction "K6_6") (pintype "input"))
      (node (ref "U8") (pin "11") (pinfunction "6_11") (pintype "unspecified"))
    )
    (net (code "27") (name "2_7") (class "Default")
      (node (ref "DISP2") (pin "5") (pinfunction "K7_5") (pintype "input"))
      (node (ref "U8") (pin "10") (pinfunction "7_10") (pintype "unspecified"))
    )
    (net (code "28") (name "2_8") (class "Default")
      (node (ref "DISP2") (pin "4") (pinfunction "K8_4") (pintype "input"))
      (node (ref "U8") (pin "1") (pinfunction "8_1") (pintype "unspecified"))
    )
    (net (code "29") (name "2_9") (class "Default")
      (node (ref "DISP2") (pin "3") (pinfunction "K9_3") (pintype "input"))
      (node (ref "U8") (pin "2") (pinfunction "9_2") (pintype "unspecified"))
    )
    (net (code "30") (name "3.3V") (class "Default")
      (node (ref "C10") (pin "2") (pinfunction "2_2") (pintype "unspecified"))
      (node (ref "C11") (pin "2") (pinfunction "2_2") (pintype "unspecified"))
      (node (ref "C12") (pin "2") (pinfunction "2_2") (pintype "unspecified"))
      (node (ref "C2") (pin "2") (pinfunction "2_2") (pintype "unspecified"))
      (node (ref "C3") (pin "2") (pinfunction "2_2") (pintype "input"))
      (node (ref "C6") (pin "2") (pinfunction "2_2") (pintype "unspecified"))
      (node (ref "D2") (pin "2") (pinfunction "A_2") (pintype "unspecified"))
      (node (ref "R14") (pin "2") (pinfunction "2_2") (pintype "input"))
      (node (ref "R15") (pin "2") (pinfunction "2_2") (pintype "input"))
      (node (ref "R16") (pin "2") (pinfunction "2_2") (pintype "input"))
      (node (ref "R2") (pin "1") (pinfunction "1_1") (pintype "input"))
      (node (ref "R4") (pin "2") (pinfunction "2_2") (pintype "input"))
      (node (ref "R5") (pin "2") (pinfunction "2_2") (pintype "input"))
      (node (ref "U1") (pin "8") (pinfunction "VCCA_8") (pintype "unspecified"))
      (node (ref "U2") (pin "3") (pinfunction "VOUT_3") (pintype "unspecified"))
      (node (ref "U3") (pin "24") (pinfunction "VDD_1_24") (pintype "unspecified"))
      (node (ref "U3") (pin "36") (pinfunction "VDD_2_36") (pintype "unspecified"))
      (node (ref "U3") (pin "48") (pinfunction "VDD_3_48") (pintype "unspecified"))
      (node (ref "U3") (pin "9") (pinfunction "VDDA_9") (pintype "unspecified"))
    )
    (net (code "31") (name "3A") (class "Default")
      (node (ref "U14") (pin "15") (pinfunction "Q0_15") (pintype "unspecified"))
      (node (ref "U9") (pin "3") (pinfunction "A_3") (pintype "unspecified"))
    )
    (net (code "32") (name "3B") (class "Default")
      (node (ref "U14") (pin "1") (pinfunction "Q1_1") (pintype "unspecified"))
      (node (ref "U9") (pin "6") (pinfunction "B_6") (pintype "unspecified"))
    )
    (net (code "33") (name "3C") (class "Default")
      (node (ref "U14") (pin "2") (pinfunction "Q2_2") (pintype "unspecified"))
      (node (ref "U9") (pin "7") (pinfunction "C_7") (pintype "unspecified"))
    )
    (net (code "34") (name "3D") (class "Default")
      (node (ref "U14") (pin "3") (pinfunction "Q3_3") (pintype "unspecified"))
      (node (ref "U9") (pin "4") (pinfunction "D_4") (pintype "unspecified"))
    )
    (net (code "35") (name "3_0") (class "Default")
      (node (ref "DISP3") (pin "2") (pinfunction "K0_2") (pintype "input"))
      (node (ref "U9") (pin "16") (pinfunction "0_16") (pintype "unspecified"))
    )
    (net (code "36") (name "3_1") (class "Default")
      (node (ref "DISP3") (pin "11") (pinfunction "K1_11") (pintype "input"))
      (node (ref "U9") (pin "15") (pinfunction "1_15") (pintype "unspecified"))
    )
    (net (code "37") (name "3_2") (class "Default")
      (node (ref "DISP3") (pin "10") (pinfunction "K2_10") (pintype "input"))
      (node (ref "U9") (pin "8") (pinfunction "2_8") (pintype "unspecified"))
    )
    (net (code "38") (name "3_3") (class "Default")
      (node (ref "DISP3") (pin "9") (pinfunction "K3_9") (pintype "input"))
      (node (ref "U9") (pin "9") (pinfunction "3_9") (pintype "unspecified"))
    )
    (net (code "39") (name "3_4") (class "Default")
      (node (ref "DISP3") (pin "8") (pinfunction "K4_8") (pintype "input"))
      (node (ref "U9") (pin "13") (pinfunction "4_13") (pintype "unspecified"))
    )
    (net (code "40") (name "3_5") (class "Default")
      (node (ref "DISP3") (pin "7") (pinfunction "K5_7") (pintype "input"))
      (node (ref "U9") (pin "14") (pinfunction "5_14") (pintype "unspecified"))
    )
    (net (code "41") (name "3_6") (class "Default")
      (node (ref "DISP3") (pin "6") (pinfunction "K6_6") (pintype "input"))
      (node (ref "U9") (pin "11") (pinfunction "6_11") (pintype "unspecified"))
    )
    (net (code "42") (name "3_7") (class "Default")
      (node (ref "DISP3") (pin "5") (pinfunction "K7_5") (pintype "input"))
      (node (ref "U9") (pin "10") (pinfunction "7_10") (pintype "unspecified"))
    )
    (net (code "43") (name "3_8") (class "Default")
      (node (ref "DISP3") (pin "4") (pinfunction "K8_4") (pintype "input"))
      (node (ref "U9") (pin "1") (pinfunction "8_1") (pintype "unspecified"))
    )
    (net (code "44") (name "3_9") (class "Default")
      (node (ref "DISP3") (pin "3") (pinfunction "K9_3") (pintype "input"))
      (node (ref "U9") (pin "2") (pinfunction "9_2") (pintype "unspecified"))
    )
    (net (code "45") (name "4A") (class "Default")
      (node (ref "U10") (pin "3") (pinfunction "A_3") (pintype "unspecified"))
      (node (ref "U14") (pin "4") (pinfunction "Q4_4") (pintype "unspecified"))
    )
    (net (code "46") (name "4B") (class "Default")
      (node (ref "U10") (pin "6") (pinfunction "B_6") (pintype "unspecified"))
      (node (ref "U14") (pin "5") (pinfunction "Q5_5") (pintype "unspecified"))
    )
    (net (code "47") (name "4C") (class "Default")
      (node (ref "U10") (pin "7") (pinfunction "C_7") (pintype "unspecified"))
      (node (ref "U14") (pin "6") (pinfunction "Q6_6") (pintype "unspecified"))
    )
    (net (code "48") (name "4D") (class "Default")
      (node (ref "U10") (pin "4") (pinfunction "D_4") (pintype "unspecified"))
      (node (ref "U14") (pin "7") (pinfunction "Q7_7") (pintype "unspecified"))
    )
    (net (code "49") (name "4_0") (class "Default")
      (node (ref "DISP4") (pin "2") (pinfunction "K0_2") (pintype "input"))
      (node (ref "U10") (pin "16") (pinfunction "0_16") (pintype "unspecified"))
    )
    (net (code "50") (name "4_1") (class "Default")
      (node (ref "DISP4") (pin "11") (pinfunction "K1_11") (pintype "input"))
      (node (ref "U10") (pin "15") (pinfunction "1_15") (pintype "unspecified"))
    )
    (net (code "51") (name "4_2") (class "Default")
      (node (ref "DISP4") (pin "10") (pinfunction "K2_10") (pintype "input"))
      (node (ref "U10") (pin "8") (pinfunction "2_8") (pintype "unspecified"))
    )
    (net (code "52") (name "4_3") (class "Default")
      (node (ref "DISP4") (pin "9") (pinfunction "K3_9") (pintype "input"))
      (node (ref "U10") (pin "9") (pinfunction "3_9") (pintype "unspecified"))
    )
    (net (code "53") (name "4_4") (class "Default")
      (node (ref "DISP4") (pin "8") (pinfunction "K4_8") (pintype "input"))
      (node (ref "U10") (pin "13") (pinfunction "4_13") (pintype "unspecified"))
    )
    (net (code "54") (name "4_5") (class "Default")
      (node (ref "DISP4") (pin "7") (pinfunction "K5_7") (pintype "input"))
      (node (ref "U10") (pin "14") (pinfunction "5_14") (pintype "unspecified"))
    )
    (net (code "55") (name "4_6") (class "Default")
      (node (ref "DISP4") (pin "6") (pinfunction "K6_6") (pintype "input"))
      (node (ref "U10") (pin "11") (pinfunction "6_11") (pintype "unspecified"))
    )
    (net (code "56") (name "4_7") (class "Default")
      (node (ref "DISP4") (pin "5") (pinfunction "K7_5") (pintype "input"))
      (node (ref "U10") (pin "10") (pinfunction "7_10") (pintype "unspecified"))
    )
    (net (code "57") (name "4_8") (class "Default")
      (node (ref "DISP4") (pin "4") (pinfunction "K8_4") (pintype "input"))
      (node (ref "U10") (pin "1") (pinfunction "8_1") (pintype "unspecified"))
    )
    (net (code "58") (name "4_9") (class "Default")
      (node (ref "DISP4") (pin "3") (pinfunction "K9_3") (pintype "input"))
      (node (ref "U10") (pin "2") (pinfunction "9_2") (pintype "unspecified"))
    )
    (net (code "59") (name "D+") (class "Default")
      (node (ref "D1") (pin "1") (pinfunction "I/O1_1") (pintype "unspecified"))
      (node (ref "U3") (pin "33") (pinfunction "PA12_33") (pintype "unspecified"))
    )
    (net (code "60") (name "D-") (class "Default")
      (node (ref "D1") (pin "3") (pinfunction "I/O2_3") (pintype "unspecified"))
      (node (ref "U3") (pin "32") (pinfunction "PA11_32") (pintype "unspecified"))
    )
    (net (code "61") (name "DM") (class "Default")
      (node (ref "D1") (pin "4") (pinfunction "I/O2_4") (pintype "unspecified"))
      (node (ref "R2") (pin "2") (pinfunction "2_2") (pintype "input"))
      (node (ref "USB1") (pin "5") (pinfunction "DN2_5") (pintype "unspecified"))
      (node (ref "USB1") (pin "7") (pinfunction "DN1_7") (pintype "unspecified"))
    )
    (net (code "62") (name "DOT_CTRL") (class "Default")
      (node (ref "R48") (pin "1") (pinfunction "1_1") (pintype "input"))
      (node (ref "R49") (pin "1") (pinfunction "1_1") (pintype "input"))
      (node (ref "U3") (pin "12") (pinfunction "PA2_12") (pintype "unspecified"))
    )
    (net (code "63") (name "DP") (class "Default")
      (node (ref "D1") (pin "6") (pinfunction "I/O1_6") (pintype "unspecified"))
      (node (ref "USB1") (pin "6") (pinfunction "DP1_6") (pintype "unspecified"))
      (node (ref "USB1") (pin "8") (pinfunction "DP2_8") (pintype "unspecified"))
    )
    (net (code "64") (name "GND") (class "Default")
      (node (ref "B1") (pin "2") (pinfunction "2_2") (pintype "input"))
      (node (ref "C1") (pin "2") (pinfunction "2_2") (pintype "input"))
      (node (ref "C10") (pin "1") (pinfunction "1_1") (pintype "unspecified"))
      (node (ref "C11") (pin "1") (pinfunction "1_1") (pintype "unspecified"))
      (node (ref "C12") (pin "1") (pinfunction "1_1") (pintype "unspecified"))
      (node (ref "C2") (pin "1") (pinfunction "1_1") (pintype "unspecified"))
      (node (ref "C3") (pin "1") (pinfunction "1_1") (pintype "input"))
      (node (ref "C4") (pin "2") (pinfunction "2_2") (pintype "input"))
      (node (ref "C5") (pin "1") (pinfunction "1_1") (pintype "unspecified"))
      (node (ref "C6") (pin "1") (pinfunction "1_1") (pintype "unspecified"))
      (node (ref "C7") (pin "1") (pinfunction "1_1") (pintype "unspecified"))
      (node (ref "C8") (pin "1") (pinfunction "1_1") (pintype "input"))
      (node (ref "C9") (pin "1") (pinfunction "1_1") (pintype "unspecified"))
      (node (ref "D1") (pin "2") (pinfunction "GND_2") (pintype "unspecified"))
      (node (ref "H1") (pin "2") (pinfunction "2_2") (pintype "unspecified"))
      (node (ref "H1") (pin "4") (pinfunction "4_4") (pintype "unspecified"))
      (node (ref "H2") (pin "3") (pinfunction "3_3") (pintype "unspecified"))
      (node (ref "H3") (pin "3") (pinfunction "3_3") (pintype "unspecified"))
      (node (ref "Q1") (pin "2") (pinfunction "E_2") (pintype "unspecified"))
      (node (ref "Q2") (pin "1") (pinfunction "E_1") (pintype "unspecified"))
      (node (ref "Q3") (pin "1") (pinfunction "E_1") (pintype "unspecified"))
      (node (ref "Q5") (pin "2") (pinfunction "E_2") (pintype "unspecified"))
      (node (ref "R1") (pin "2") (pinfunction "2_2") (pintype "input"))
      (node (ref "R13") (pin "1") (pinfunction "1_1") (pintype "input"))
      (node (ref "R17") (pin "1") (pinfunction "1_1") (pintype "input"))
      (node (ref "R22") (pin "1") (pinfunction "1_1") (pintype "input"))
      (node (ref "R23") (pin "1") (pinfunction "1_1") (pintype "input"))
      (node (ref "R3") (pin "2") (pinfunction "2_2") (pintype "input"))
      (node (ref "R32") (pin "2") (pinfunction "2_2") (pintype "input"))
      (node (ref "R33") (pin "2") (pinfunction "2_2") (pintype "input"))
      (node (ref "R6") (pin "1") (pinfunction "1_1") (pintype "input"))
      (node (ref "R9") (pin "1") (pinfunction "1_1") (pintype "input"))
      (node (ref "U1") (pin "5") (pinfunction "GND_5") (pintype "unspecified"))
      (node (ref "U10") (pin "12") (pinfunction "GND_12") (pintype "unspecified"))
      (node (ref "U13") (pin "8") (pinfunction "GND_8") (pintype "unspecified"))
      (node (ref "U14") (pin "8") (pinfunction "GND_8") (pintype "unspecified"))
      (node (ref "U2") (pin "1") (pinfunction "VSS_1") (pintype "unspecified"))
      (node (ref "U3") (pin "23") (pinfunction "VSS_1_23") (pintype "unspecified"))
      (node (ref "U3") (pin "35") (pinfunction "VSS_2_35") (pintype "unspecified"))
      (node (ref "U3") (pin "47") (pinfunction "VSS_3_47") (pintype "unspecified"))
      (node (ref "U3") (pin "8") (pinfunction "VSSA_8") (pintype "unspecified"))
      (node (ref "U7") (pin "12") (pinfunction "GND_12") (pintype "unspecified"))
      (node (ref "U8") (pin "12") (pinfunction "GND_12") (pintype "unspecified"))
      (node (ref "U9") (pin "12") (pinfunction "GND_12") (pintype "unspecified"))
      (node (ref "USB1") (pin "1") (pinfunction "GND_1") (pintype "unspecified"))
      (node (ref "USB1") (pin "12") (pinfunction "GND_12") (pintype "unspecified"))
    )
    (net (code "65") (name "HV") (class "Default")
      (node (ref "H1") (pin "1") (pinfunction "1_1") (pintype "unspecified"))
      (node (ref "R26") (pin "1") (pinfunction "1_1") (pintype "input"))
      (node (ref "R27") (pin "1") (pinfunction "1_1") (pintype "input"))
      (node (ref "R28") (pin "1") (pinfunction "1_1") (pintype "input"))
      (node (ref "R29") (pin "1") (pinfunction "1_1") (pintype "input"))
      (node (ref "R30") (pin "2") (pinfunction "2_2") (pintype "input"))
      (node (ref "R31") (pin "2") (pinfunction "2_2") (pintype "input"))
    )
    (net (code "66") (name "HV_ENABLE") (class "Default")
      (node (ref "R12") (pin "2") (pinfunction "2_2") (pintype "input"))
      (node (ref "U3") (pin "20") (pinfunction "PB2_20") (pintype "unspecified"))
    )
    (net (code "67") (name "MCU_STCP") (class "Default")
      (node (ref "R8") (pin "1") (pinfunction "1_1") (pintype "input"))
      (node (ref "U3") (pin "13") (pinfunction "PA3_13") (pintype "unspecified"))
    )
    (net (code "68") (name "Net-(D2-C)") (class "Default")
      (node (ref "C5") (pin "2") (pinfunction "2_2") (pintype "unspecified"))
      (node (ref "D2") (pin "1") (pinfunction "C_1") (pintype "unspecified"))
      (node (ref "D3") (pin "1") (pinfunction "C_1") (pintype "unspecified"))
      (node (ref "U3") (pin "1") (pinfunction "VBAT_1") (pintype "unspecified"))
    )
    (net (code "69") (name "Net-(D3-A)") (class "Default")
      (node (ref "B1") (pin "1") (pinfunction "1_1") (pintype "input"))
      (node (ref "D3") (pin "2") (pinfunction "A_2") (pintype "unspecified"))
    )
    (net (code "70") (name "Net-(DISP1-ANODE)") (class "Default")
      (node (ref "DISP1") (pin "1") (pinfunction "ANODE_1") (pintype "input"))
      (node (ref "R26") (pin "2") (pinfunction "2_2") (pintype "input"))
    )
    (net (code "71") (name "Net-(DISP2-ANODE)") (class "Default")
      (node (ref "DISP2") (pin "1") (pinfunction "ANODE_1") (pintype "input"))
      (node (ref "R27") (pin "2") (pinfunction "2_2") (pintype "input"))
    )
    (net (code "72") (name "Net-(DISP3-ANODE)") (class "Default")
      (node (ref "DISP3") (pin "1") (pinfunction "ANODE_1") (pintype "input"))
      (node (ref "R28") (pin "2") (pinfunction "2_2") (pintype "input"))
    )
    (net (code "73") (name "Net-(DISP4-ANODE)") (class "Default")
      (node (ref "DISP4") (pin "1") (pinfunction "ANODE_1") (pintype "input"))
      (node (ref "R29") (pin "2") (pinfunction "2_2") (pintype "input"))
    )
    (net (code "74") (name "Net-(NE1-Pad1)") (class "Default")
      (node (ref "NE1") (pin "1") (pinfunction "1_1") (pintype "unspecified"))
      (node (ref "R30") (pin "1") (pinfunction "1_1") (pintype "input"))
    )
    (net (code "75") (name "Net-(NE2-Pad1)") (class "Default")
      (node (ref "NE2") (pin "1") (pinfunction "1_1") (pintype "unspecified"))
      (node (ref "R31") (pin "1") (pinfunction "1_1") (pintype "input"))
    )
    (net (code "76") (name "Net-(Q1-B)") (class "Default")
      (node (ref "Q1") (pin "1") (pinfunction "B_1") (pintype "unspecified"))
      (node (ref "R8") (pin "2") (pinfunction "2_2") (pintype "input"))
      (node (ref "R9") (pin "2") (pinfunction "2_2") (pintype "input"))
    )
    (net (code "77") (name "Net-(Q2-B)") (class "Default")
      (node (ref "Q2") (pin "2") (pinfunction "B_2") (pintype "unspecified"))
      (node (ref "R32") (pin "1") (pinfunction "1_1") (pintype "input"))
      (node (ref "R49") (pin "2") (pinfunction "2_2") (pintype "input"))
    )
    (net (code "78") (name "Net-(Q2-C)") (class "Default")
      (node (ref "NE1") (pin "2") (pinfunction "2_2") (pintype "unspecified"))
      (node (ref "Q2") (pin "3") (pinfunction "C_3") (pintype "unspecified"))
    )
    (net (code "79") (name "Net-(Q3-B)") (class "Default")
      (node (ref "Q3") (pin "2") (pinfunction "B_2") (pintype "unspecified"))
      (node (ref "R33") (pin "1") (pinfunction "1_1") (pintype "input"))
      (node (ref "R48") (pin "2") (pinfunction "2_2") (pintype "input"))
    )
    (net (code "80") (name "Net-(Q3-C)") (class "Default")
      (node (ref "NE2") (pin "2") (pinfunction "2_2") (pintype "unspecified"))
      (node (ref "Q3") (pin "3") (pinfunction "C_3") (pintype "unspecified"))
    )
    (net (code "81") (name "Net-(Q4-B)") (class "Default")
      (node (ref "Q4") (pin "1") (pinfunction "B_1") (pintype "unspecified"))
      (node (ref "R10") (pin "1") (pinfunction "1_1") (pintype "input"))
      (node (ref "R11") (pin "2") (pinfunction "2_2") (pintype "input"))
    )
    (net (code "82") (name "Net-(Q4-E)") (class "Default")
      (node (ref "H1") (pin "5") (pinfunction "5_5") (pintype "unspecified"))
      (node (ref "Q4") (pin "2") (pinfunction "E_2") (pintype "unspecified"))
    )
    (net (code "83") (name "Net-(Q5-B)") (class "Default")
      (node (ref "Q5") (pin "1") (pinfunction "B_1") (pintype "unspecified"))
      (node (ref "R12") (pin "1") (pinfunction "1_1") (pintype "input"))
      (node (ref "R13") (pin "2") (pinfunction "2_2") (pintype "input"))
    )
    (net (code "84") (name "Net-(Q5-C)") (class "Default")
      (node (ref "Q5") (pin "3") (pinfunction "C_3") (pintype "unspecified"))
      (node (ref "R11") (pin "1") (pinfunction "1_1") (pintype "input"))
    )
    (net (code "85") (name "Net-(U1-OE)") (class "Default")
      (node (ref "R4") (pin "1") (pinfunction "1_1") (pintype "input"))
      (node (ref "U1") (pin "4") (pinfunction "OE_4") (pintype "unspecified"))
    )
    (net (code "86") (name "Net-(U3-BOOT0)") (class "Default")
      (node (ref "R6") (pin "2") (pinfunction "2_2") (pintype "input"))
      (node (ref "U3") (pin "44") (pinfunction "BOOT0_44") (pintype "unspecified"))
    )
    (net (code "87") (name "Net-(U3-NRST)") (class "Default")
      (node (ref "C9") (pin "2") (pinfunction "2_2") (pintype "unspecified"))
      (node (ref "R5") (pin "1") (pinfunction "1_1") (pintype "input"))
      (node (ref "U3") (pin "7") (pinfunction "NRST_7") (pintype "unspecified"))
    )
    (net (code "88") (name "Net-(U3-PC14-OSC32_IN)") (class "Default")
      (node (ref "C1") (pin "1") (pinfunction "1_1") (pintype "input"))
      (node (ref "U3") (pin "3") (pinfunction "PC14-OSC32_IN_3") (pintype "unspecified"))
      (node (ref "X1") (pin "2") (pinfunction "2_2") (pintype "unspecified"))
    )
    (net (code "89") (name "Net-(U3-PC15-OSC32_OUT)") (class "Default")
      (node (ref "C4") (pin "1") (pinfunction "1_1") (pintype "input"))
      (node (ref "U3") (pin "4") (pinfunction "PC15-OSC32_OUT_4") (pintype "unspecified"))
      (node (ref "X1") (pin "1") (pinfunction "1_1") (pintype "unspecified"))
    )
    (net (code "90") (name "Net-(U13-MR#)") (class "Default")
      (node (ref "R24") (pin "2") (pinfunction "2_2") (pintype "input"))
      (node (ref "U13") (pin "10") (pinfunction "MR#_10") (pintype "unspecified"))
    )
    (net (code "91") (name "Net-(U13-OE#)") (class "Default")
      (node (ref "R22") (pin "2") (pinfunction "2_2") (pintype "input"))
      (node (ref "U13") (pin "13") (pinfunction "OE#_13") (pintype "unspecified"))
    )
    (net (code "92") (name "Net-(U13-Q7S)") (class "Default")
      (node (ref "U13") (pin "9") (pinfunction "Q7S_9") (pintype "unspecified"))
      (node (ref "U14") (pin "14") (pinfunction "DS_14") (pintype "unspecified"))
    )
    (net (code "93") (name "Net-(U14-MR#)") (class "Default")
      (node (ref "R25") (pin "2") (pinfunction "2_2") (pintype "input"))
      (node (ref "U14") (pin "10") (pinfunction "MR#_10") (pintype "unspecified"))
    )
    (net (code "94") (name "Net-(U14-OE#)") (class "Default")
      (node (ref "R23") (pin "2") (pinfunction "2_2") (pintype "input"))
      (node (ref "U14") (pin "13") (pinfunction "OE#_13") (pintype "unspecified"))
    )
    (net (code "95") (name "Net-(USB1-CC1)") (class "Default")
      (node (ref "R3") (pin "1") (pinfunction "1_1") (pintype "input"))
      (node (ref "USB1") (pin "4") (pinfunction "CC1_4") (pintype "unspecified"))
    )
    (net (code "96") (name "Net-(USB1-CC2)") (class "Default")
      (node (ref "R1") (pin "1") (pinfunction "1_1") (pintype "input"))
      (node (ref "USB1") (pin "10") (pinfunction "CC2_10") (pintype "unspecified"))
    )
    (net (code "97") (name "SPI1_MOSI") (class "Default")
      (node (ref "U1") (pin "6") (pinfunction "A2_6") (pintype "unspecified"))
      (node (ref "U3") (pin "17") (pinfunction "PA7_17") (pintype "unspecified"))
    )
    (net (code "98") (name "SPI1_SCK") (class "Default")
      (node (ref "U1") (pin "7") (pinfunction "A1_7") (pintype "unspecified"))
      (node (ref "U3") (pin "15") (pinfunction "PA5_15") (pintype "unspecified"))
    )
    (net (code "99") (name "SPI_CLK") (class "Default")
      (node (ref "U1") (pin "2") (pinfunction "B1_2") (pintype "unspecified"))
      (node (ref "U13") (pin "11") (pinfunction "SHCP_11") (pintype "unspecified"))
      (node (ref "U14") (pin "11") (pinfunction "SHCP_11") (pintype "unspecified"))
    )
    (net (code "100") (name "SPI_MOSI") (class "Default")
      (node (ref "U1") (pin "3") (pinfunction "B2_3") (pintype "unspecified"))
      (node (ref "U13") (pin "14") (pinfunction "DS_14") (pintype "unspecified"))
    )
    (net (code "101") (name "STCP") (class "Default")
      (node (ref "Q1") (pin "3") (pinfunction "C_3") (pintype "unspecified"))
      (node (ref "R7") (pin "1") (pinfunction "1_1") (pintype "input"))
      (node (ref "U13") (pin "12") (pinfunction "STCP_12") (pintype "unspecified"))
      (node (ref "U14") (pin "12") (pinfunction "STCP_12") (pintype "unspecified"))
    )
    (net (code "102") (name "SWCLK") (class "Default")
      (node (ref "H2") (pin "1") (pinfunction "1_1") (pintype "unspecified"))
      (node (ref "R17") (pin "2") (pinfunction "2_2") (pintype "input"))
      (node (ref "U3") (pin "37") (pinfunction "PA14_37") (pintype "unspecified"))
    )
    (net (code "103") (name "SWDIO") (class "Default")
      (node (ref "H2") (pin "2") (pinfunction "2_2") (pintype "unspecified"))
      (node (ref "R14") (pin "1") (pinfunction "1_1") (pintype "input"))
      (node (ref "U3") (pin "34") (pinfunction "PA13_34") (pintype "unspecified"))
    )
    (net (code "104") (name "UART1_RX") (class "Default")
      (node (ref "H3") (pin "1") (pinfunction "1_1") (pintype "unspecified"))
      (node (ref "R16") (pin "1") (pinfunction "1_1") (pintype "input"))
      (node (ref "U3") (pin "31") (pinfunction "PA10_31") (pintype "unspecified"))
    )
    (net (code "105") (name "UART1_TX") (class "Default")
      (node (ref "H3") (pin "2") (pinfunction "2_2") (pintype "unspecified"))
      (node (ref "R15") (pin "1") (pinfunction "1_1") (pintype "input"))
      (node (ref "U3") (pin "30") (pinfunction "PA9_30") (pintype "unspecified"))
    )
    (net (code "106") (name "unconnected-(H1-Pad3)") (class "Default")
      (node (ref "H1") (pin "3") (pinfunction "3_3") (pintype "unspecified+no_connect"))
    )
    (net (code "107") (name "unconnected-(U3-PA0-WKUP-Pad10)") (class "Default")
      (node (ref "U3") (pin "10") (pinfunction "PA0-WKUP_10") (pintype "unspecified+no_connect"))
    )
    (net (code "108") (name "unconnected-(U3-PA1-Pad11)") (class "Default")
      (node (ref "U3") (pin "11") (pinfunction "PA1_11") (pintype "unspecified+no_connect"))
    )
    (net (code "109") (name "unconnected-(U3-PA4-Pad14)") (class "Default")
      (node (ref "U3") (pin "14") (pinfunction "PA4_14") (pintype "unspecified+no_connect"))
    )
    (net (code "110") (name "unconnected-(U3-PA6-Pad16)") (class "Default")
      (node (ref "U3") (pin "16") (pinfunction "PA6_16") (pintype "unspecified+no_connect"))
    )
    (net (code "111") (name "unconnected-(U3-PA8-Pad29)") (class "Default")
      (node (ref "U3") (pin "29") (pinfunction "PA8_29") (pintype "unspecified+no_connect"))
    )
    (net (code "112") (name "unconnected-(U3-PA15-Pad38)") (class "Default")
      (node (ref "U3") (pin "38") (pinfunction "PA15_38") (pintype "unspecified+no_connect"))
    )
    (net (code "113") (name "unconnected-(U3-PB0-Pad18)") (class "Default")
      (node (ref "U3") (pin "18") (pinfunction "PB0_18") (pintype "unspecified+no_connect"))
    )
    (net (code "114") (name "unconnected-(U3-PB1-Pad19)") (class "Default")
      (node (ref "U3") (pin "19") (pinfunction "PB1_19") (pintype "unspecified+no_connect"))
    )
    (net (code "115") (name "unconnected-(U3-PB3-Pad39)") (class "Default")
      (node (ref "U3") (pin "39") (pinfunction "PB3_39") (pintype "unspecified+no_connect"))
    )
    (net (code "116") (name "unconnected-(U3-PB4-Pad40)") (class "Default")
      (node (ref "U3") (pin "40") (pinfunction "PB4_40") (pintype "unspecified+no_connect"))
    )
    (net (code "117") (name "unconnected-(U3-PB5-Pad41)") (class "Default")
      (node (ref "U3") (pin "41") (pinfunction "PB5_41") (pintype "unspecified+no_connect"))
    )
    (net (code "118") (name "unconnected-(U3-PB6-Pad42)") (class "Default")
      (node (ref "U3") (pin "42") (pinfunction "PB6_42") (pintype "unspecified+no_connect"))
    )
    (net (code "119") (name "unconnected-(U3-PB7-Pad43)") (class "Default")
      (node (ref "U3") (pin "43") (pinfunction "PB7_43") (pintype "unspecified+no_connect"))
    )
    (net (code "120") (name "unconnected-(U3-PB8-Pad45)") (class "Default")
      (node (ref "U3") (pin "45") (pinfunction "PB8_45") (pintype "unspecified+no_connect"))
    )
    (net (code "121") (name "unconnected-(U3-PB9-Pad46)") (class "Default")
      (node (ref "U3") (pin "46") (pinfunction "PB9_46") (pintype "unspecified+no_connect"))
    )
    (net (code "122") (name "unconnected-(U3-PB10-Pad21)") (class "Default")
      (node (ref "U3") (pin "21") (pinfunction "PB10_21") (pintype "unspecified+no_connect"))
    )
    (net (code "123") (name "unconnected-(U3-PB11-Pad22)") (class "Default")
      (node (ref "U3") (pin "22") (pinfunction "PB11_22") (pintype "unspecified+no_connect"))
    )
    (net (code "124") (name "unconnected-(U3-PB12-Pad25)") (class "Default")
      (node (ref "U3") (pin "25") (pinfunction "PB12_25") (pintype "unspecified+no_connect"))
    )
    (net (code "125") (name "unconnected-(U3-PB13-Pad26)") (class "Default")
      (node (ref "U3") (pin "26") (pinfunction "PB13_26") (pintype "unspecified+no_connect"))
    )
    (net (code "126") (name "unconnected-(U3-PB14-Pad27)") (class "Default")
      (node (ref "U3") (pin "27") (pinfunction "PB14_27") (pintype "unspecified+no_connect"))
    )
    (net (code "127") (name "unconnected-(U3-PB15-Pad28)") (class "Default")
      (node (ref "U3") (pin "28") (pinfunction "PB15_28") (pintype "unspecified+no_connect"))
    )
    (net (code "128") (name "unconnected-(U3-PC13-TAMPER-RTC-Pad2)") (class "Default")
      (node (ref "U3") (pin "2") (pinfunction "PC13-TAMPER-RTC_2") (pintype "unspecified+no_connect"))
    )
    (net (code "129") (name "unconnected-(U3-PD0-OSC_IN-Pad5)") (class "Default")
      (node (ref "U3") (pin "5") (pinfunction "PD0-OSC_IN_5") (pintype "unspecified+no_connect"))
    )
    (net (code "130") (name "unconnected-(U3-PD1-OSC_OUT-Pad6)") (class "Default")
      (node (ref "U3") (pin "6") (pinfunction "PD1-OSC_OUT_6") (pintype "unspecified+no_connect"))
    )
    (net (code "131") (name "unconnected-(U14-Q7S-Pad9)") (class "Default")
      (node (ref "U14") (pin "9") (pinfunction "Q7S_9") (pintype "unspecified+no_connect"))
    )
    (net (code "132") (name "unconnected-(USB1-SBU1-Pad9)") (class "Default")
      (node (ref "USB1") (pin "9") (pinfunction "SBU1_9") (pintype "unspecified+no_connect"))
    )
    (net (code "133") (name "unconnected-(USB1-SBU2-Pad3)") (class "Default")
      (node (ref "USB1") (pin "3") (pinfunction "SBU2_3") (pintype "unspecified+no_connect"))
    )
    (net (code "134") (name "unconnected-(USB1-SHELL-Pad13)") (class "Default")
      (node (ref "USB1") (pin "13") (pinfunction "SHELL_13") (pintype "unspecified+no_connect"))
    )
    (net (code "135") (name "unconnected-(USB1-SHELL-Pad14)") (class "Default")
      (node (ref "USB1") (pin "14") (pinfunction "SHELL_14") (pintype "unspecified+no_connect"))
    )
  )
)
